# Sheet2.net
KiCad netlist of a schematic drawn in Altium Designer
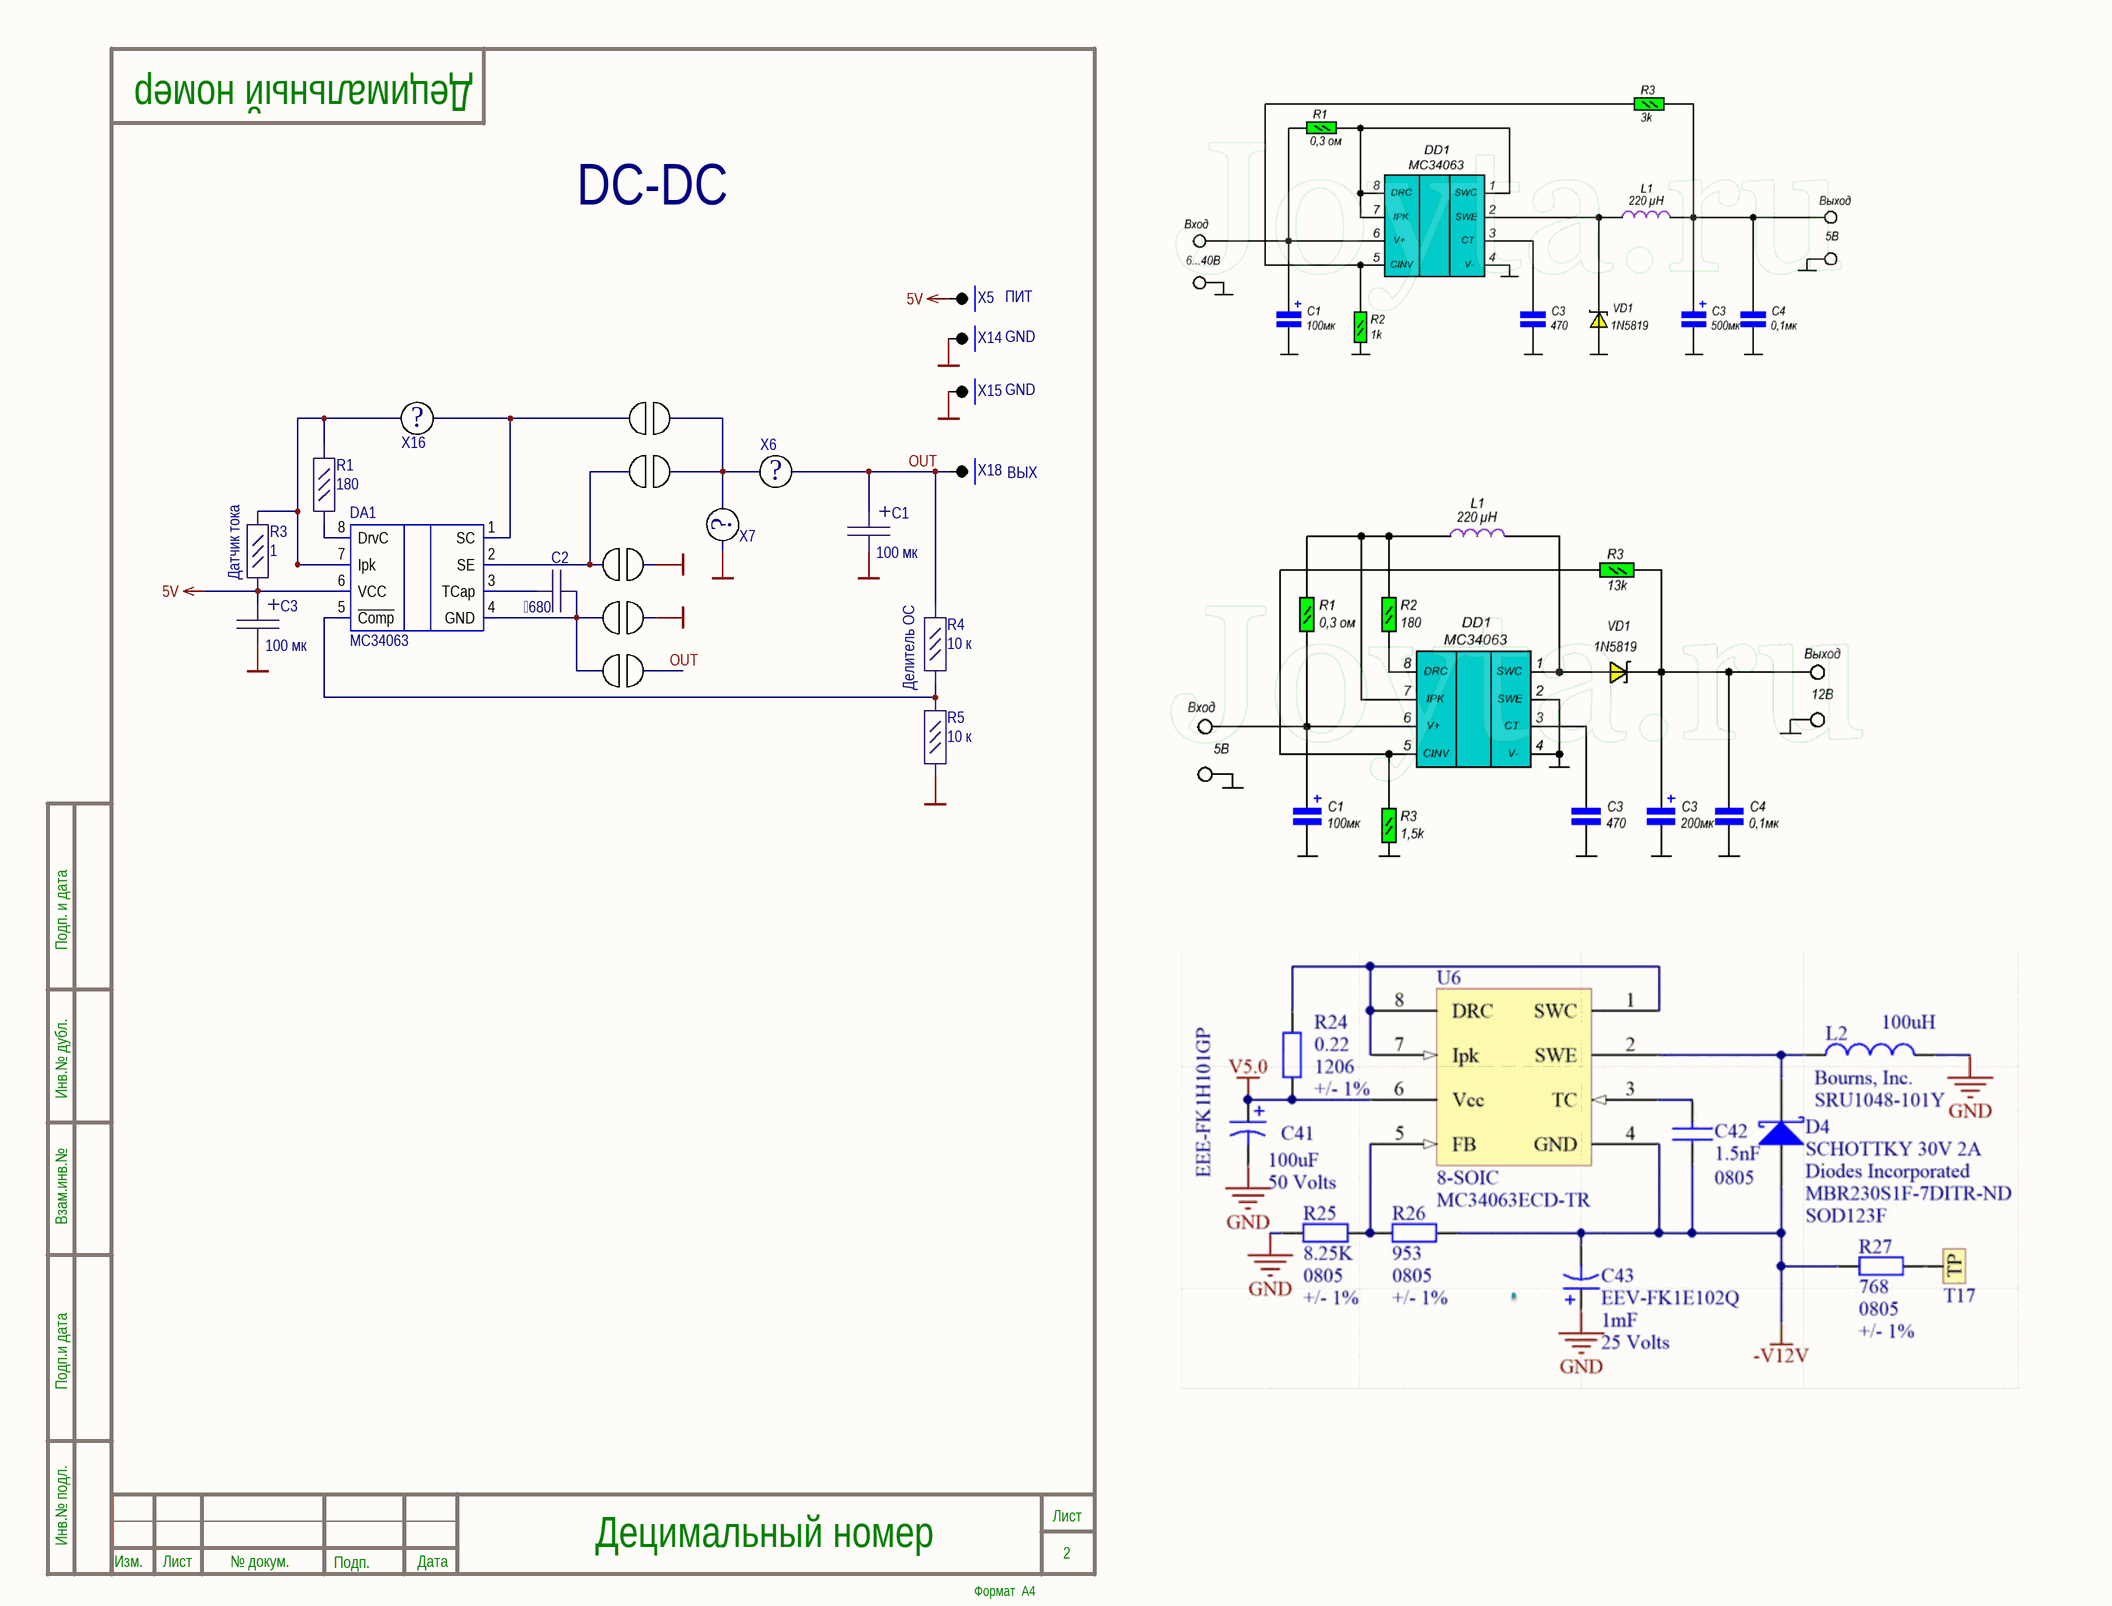
[diagram p0: Sheet2.SchDoc]

(export (version "E")
  (design (tool "Eeschema 10.0.6"))
  (components
    (comp (ref "C1")
      (value "100 мк")
      (footprint "B_CASE")
      (description "CAP TANT 100UF 10% 4V 1411")
      (fields (field (name "PART NUMBER") "TAJB107K004RNJ") (field (name "MANUFACTURER") "AVX Corporation"))
      (libsource (lib "Database_Lib") (part "Tantalum Capacitor"))
    )
    (comp (ref "C2")
      (value "680")
      (footprint "C_0603")
      (description "CAP CER 0.1UF 100V X7R 0603")
      (fields
        (field (name "PART NUMBER") "GRM188R72A104KA35D")
        (field (name "MANUFACTURER") "Murata Electronics")
      )
      (libsource (lib "Database_Lib") (part "Capasitor"))
    )
    (comp (ref "C3")
      (value "100 мк")
      (footprint "B_CASE")
      (description "CAP TANT 100UF 10% 4V 1411")
      (fields (field (name "PART NUMBER") "TAJB107K004RNJ") (field (name "MANUFACTURER") "AVX Corporation"))
      (libsource (lib "Database_Lib") (part "Tantalum Capacitor"))
    )
    (comp (ref "DA1") (value "MC34063") (footprint "SO-8") (libsource (lib "6.Chips") (part "MC34063")))
    (comp (ref "R1")
      (value "180")
      (footprint "R_0603")
      (description "RES SMD 10K OHM 1% 1/10W 0603")
      (fields (field (name "PART NUMBER") "CR0603-FX-1002ELF") (field (name "MANUFACTURER") "Bourns Inc."))
      (libsource (lib "Database_Lib") (part "Resistor"))
    )
    (comp (ref "R3")
      (value "1")
      (footprint "R_0603")
      (description "RES SMD 10K OHM 1% 1/10W 0603")
      (fields (field (name "PART NUMBER") "CR0603-FX-1002ELF") (field (name "MANUFACTURER") "Bourns Inc."))
      (libsource (lib "Database_Lib") (part "Resistor"))
    )
    (comp (ref "R4")
      (value "10 к")
      (footprint "R_0603")
      (description "RES SMD 10K OHM 1% 1/10W 0603")
      (fields (field (name "PART NUMBER") "CR0603-FX-1002ELF") (field (name "MANUFACTURER") "Bourns Inc."))
      (libsource (lib "Database_Lib") (part "Resistor"))
    )
    (comp (ref "R5")
      (value "10 к")
      (footprint "R_0603")
      (description "RES SMD 10K OHM 1% 1/10W 0603")
      (fields (field (name "PART NUMBER") "CR0603-FX-1002ELF") (field (name "MANUFACTURER") "Bourns Inc."))
      (libsource (lib "Database_Lib") (part "Resistor"))
    )
    (comp (ref "X5") (value "КТ") (footprint "KT") (libsource (lib "7.Connectors") (part "КТ")))
    (comp (ref "X6") (value "U-C") (footprint "unknown component") (libsource (lib "11.Other") (part "U-C")))
    (comp (ref "X7") (value "U-C") (footprint "unknown component") (libsource (lib "11.Other") (part "U-C")))
    (comp (ref "X8")
      (value "Solder_jumper")
      (footprint "Solder_jumper")
      (libsource (lib "11.Other") (part "Solder_jumper"))
    )
    (comp (ref "X9")
      (value "Solder_jumper")
      (footprint "Solder_jumper")
      (libsource (lib "11.Other") (part "Solder_jumper"))
    )
    (comp (ref "X10")
      (value "Solder_jumper")
      (footprint "Solder_jumper")
      (libsource (lib "11.Other") (part "Solder_jumper"))
    )
    (comp (ref "X14") (value "КТ") (footprint "KT") (libsource (lib "7.Connectors") (part "КТ")))
    (comp (ref "X15") (value "КТ") (footprint "KT") (libsource (lib "7.Connectors") (part "КТ")))
    (comp (ref "X16") (value "U-C") (footprint "unknown component") (libsource (lib "11.Other") (part "U-C")))
    (comp (ref "X17")
      (value "Solder_jumper")
      (footprint "Solder_jumper")
      (libsource (lib "11.Other") (part "Solder_jumper"))
    )
    (comp (ref "X18") (value "КТ") (footprint "KT") (libsource (lib "7.Connectors") (part "КТ")))
    (comp (ref "X19")
      (value "Solder_jumper")
      (footprint "Solder_jumper")
      (libsource (lib "11.Other") (part "Solder_jumper"))
    )
  )
  (nets
    (net (code "1") (name "/OUT") (class "Default")
      (node (ref "C1") (pin "1") (pinfunction "1_1") (pintype "passive"))
      (node (ref "R4") (pin "1") (pinfunction "1_1") (pintype "passive"))
      (node (ref "X10") (pin "1") (pinfunction "1_1") (pintype "passive"))
      (node (ref "X18") (pin "1") (pinfunction "1_1") (pintype "passive"))
      (node (ref "X6") (pin "2") (pinfunction "2_2") (pintype "passive"))
    )
    (net (code "2") (name "5V") (class "Default")
      (node (ref "C3") (pin "1") (pinfunction "1_1") (pintype "passive"))
      (node (ref "DA1") (pin "6") (pinfunction "VCC_6") (pintype "passive"))
      (node (ref "R3") (pin "2") (pinfunction "2_2") (pintype "passive"))
      (node (ref "X5") (pin "1") (pinfunction "1_1") (pintype "passive"))
    )
    (net (code "3") (name "GND") (class "Default")
      (node (ref "C1") (pin "2") (pinfunction "2_2") (pintype "passive"))
      (node (ref "C3") (pin "2") (pinfunction "2_2") (pintype "passive"))
      (node (ref "R5") (pin "2") (pinfunction "2_2") (pintype "passive"))
      (node (ref "X14") (pin "1") (pinfunction "1_1") (pintype "passive"))
      (node (ref "X15") (pin "1") (pinfunction "1_1") (pintype "passive"))
      (node (ref "X19") (pin "2") (pinfunction "2_2") (pintype "passive"))
      (node (ref "X7") (pin "1") (pinfunction "1_1") (pintype "passive"))
      (node (ref "X9") (pin "2") (pinfunction "2_2") (pintype "passive"))
    )
    (net (code "4") (name "Net-(DA1-DrvC)") (class "Default")
      (node (ref "DA1") (pin "8") (pinfunction "DrvC_8") (pintype "passive"))
      (node (ref "R1") (pin "2") (pinfunction "2_2") (pintype "passive"))
    )
    (net (code "5") (name "Net-(DA1-GND)") (class "Default")
      (node (ref "C2") (pin "1") (pinfunction "1_1") (pintype "passive"))
      (node (ref "DA1") (pin "4") (pinfunction "GND_4") (pintype "passive"))
      (node (ref "X10") (pin "2") (pinfunction "2_2") (pintype "passive"))
      (node (ref "X9") (pin "1") (pinfunction "1_1") (pintype "passive"))
    )
    (net (code "6") (name "Net-(DA1-Ipk)") (class "Default")
      (node (ref "DA1") (pin "7") (pinfunction "Ipk_7") (pintype "passive"))
      (node (ref "R1") (pin "1") (pinfunction "1_1") (pintype "passive"))
      (node (ref "R3") (pin "1") (pinfunction "1_1") (pintype "passive"))
      (node (ref "X16") (pin "1") (pinfunction "1_1") (pintype "passive"))
    )
    (net (code "7") (name "Net-(DA1-SC)") (class "Default")
      (node (ref "DA1") (pin "1") (pinfunction "SC_1") (pintype "passive"))
      (node (ref "X16") (pin "2") (pinfunction "2_2") (pintype "passive"))
      (node (ref "X17") (pin "1") (pinfunction "1_1") (pintype "passive"))
    )
    (net (code "8") (name "Net-(DA1-SE)") (class "Default")
      (node (ref "DA1") (pin "2") (pinfunction "SE_2") (pintype "passive"))
      (node (ref "X19") (pin "1") (pinfunction "1_1") (pintype "passive"))
      (node (ref "X8") (pin "1") (pinfunction "1_1") (pintype "passive"))
    )
    (net (code "9") (name "Net-(DA1-TCap)") (class "Default")
      (node (ref "C2") (pin "2") (pinfunction "2_2") (pintype "passive"))
      (node (ref "DA1") (pin "3") (pinfunction "TCap_3") (pintype "passive"))
    )
    (net (code "10") (name "Net-(DA1-~{Comp})") (class "Default")
      (node (ref "DA1") (pin "5") (pinfunction "~{Comp}_5") (pintype "passive"))
      (node (ref "R4") (pin "2") (pinfunction "2_2") (pintype "passive"))
      (node (ref "R5") (pin "1") (pinfunction "1_1") (pintype "passive"))
    )
    (net (code "11") (name "Net-(X17-Pad2)") (class "Default")
      (node (ref "X17") (pin "2") (pinfunction "2_2") (pintype "passive"))
      (node (ref "X6") (pin "1") (pinfunction "1_1") (pintype "passive"))
      (node (ref "X7") (pin "2") (pinfunction "2_2") (pintype "passive"))
      (node (ref "X8") (pin "2") (pinfunction "2_2") (pintype "passive"))
    )
  )
)
